# OTA.net
KiCad netlist of a schematic drawn in Altium Designer
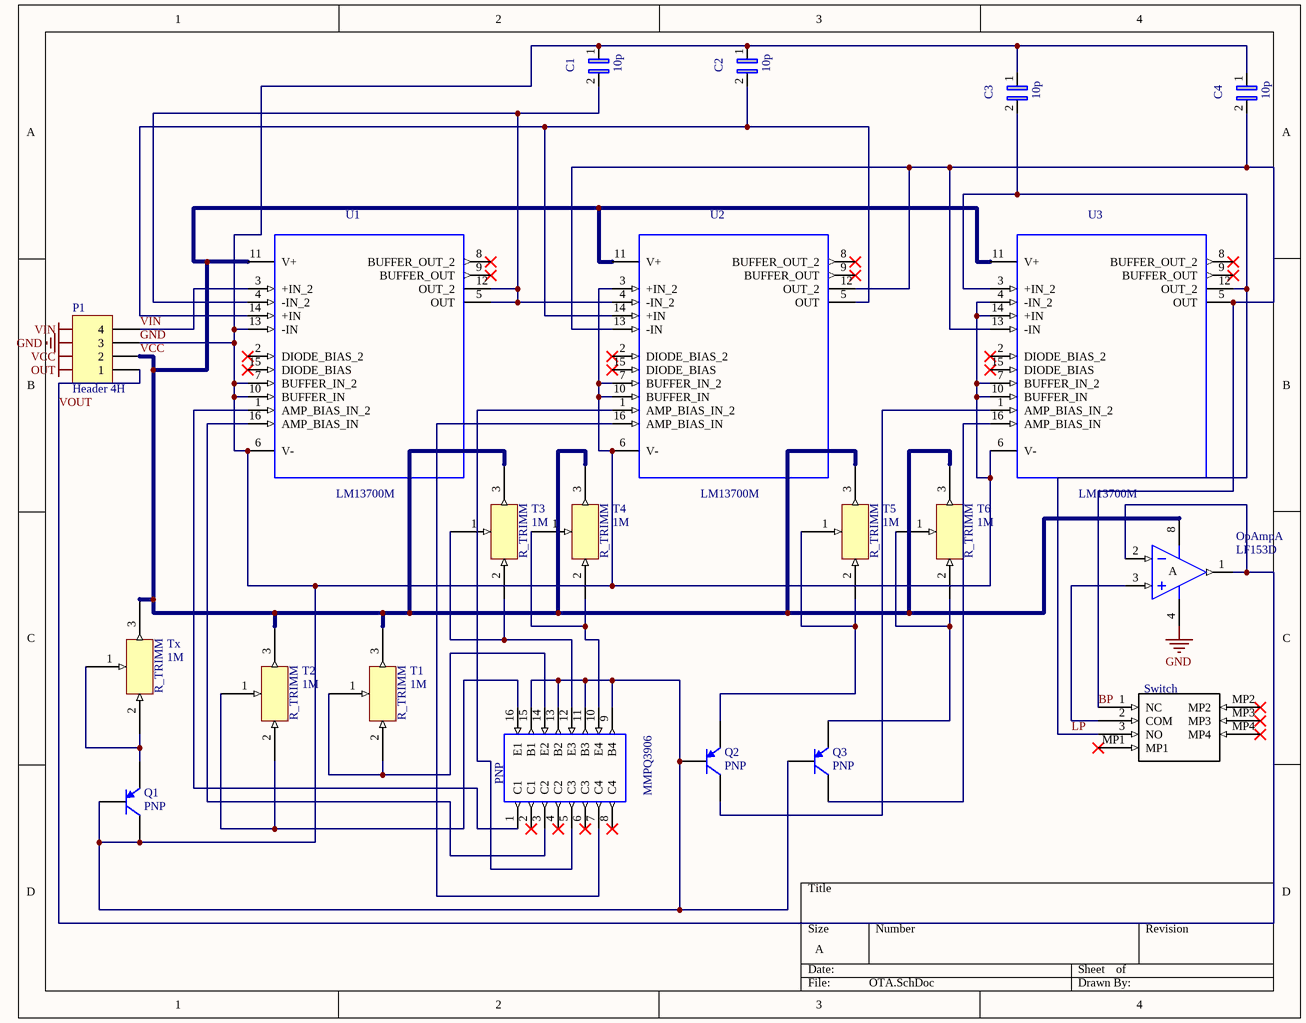
[diagram p0: OTA.SchDoc]

(export (version "E")
  (design (tool "Eeschema 10.0.6"))
  (components
    (comp (ref "C1")
      (value "10p")
      (footprint "_C*CAPC1005X55N_CC0402C100K5GACAUTO_CPrimary_C")
      (description "CAPACITOR CERAMIC 10 PF 10% TOL 50V C0G 0402")
      (fields (field (name "MF") "KEMET") (field (name "MP") "C0402C100K5GACAUTO"))
      (libsource (lib "*") (part "C0402C100K5GACAUTO"))
    )
    (comp (ref "C2")
      (value "10p")
      (footprint "_C*CAPC1005X55N_CC0402C100K5GACAUTO_CPrimary_C")
      (description "CAPACITOR CERAMIC 10 PF 10% TOL 50V C0G 0402")
      (fields (field (name "MF") "KEMET") (field (name "MP") "C0402C100K5GACAUTO"))
      (libsource (lib "*") (part "C0402C100K5GACAUTO"))
    )
    (comp (ref "C3")
      (value "10p")
      (footprint "_C*CAPC1005X55N_CC0402C100K5GACAUTO_CPrimary_C")
      (description "CAPACITOR CERAMIC 10 PF 10% TOL 50V C0G 0402")
      (fields (field (name "MF") "KEMET") (field (name "MP") "C0402C100K5GACAUTO"))
      (libsource (lib "*") (part "C0402C100K5GACAUTO"))
    )
    (comp (ref "C4")
      (value "10p")
      (footprint "_C*CAPC1005X55N_CC0402C100K5GACAUTO_CPrimary_C")
      (description "CAPACITOR CERAMIC 10 PF 10% TOL 50V C0G 0402")
      (fields (field (name "MF") "KEMET") (field (name "MP") "C0402C100K5GACAUTO"))
      (libsource (lib "*") (part "C0402C100K5GACAUTO"))
    )
    (comp (ref "OpAmp")
      (value "LF153D")
      (footprint "SO8_N")
      (description "Wide-Bandwidth Dual J-FET Operational Amplifier")
      (fields (field (name "PUBLISHER") "Altium Limited"))
      (libsource (lib "ST Operational Amplifier") (part "LF153D"))
    )
    (comp (ref "P1")
      (value "Header 4H")
      (footprint "HDR1X4H")
      (description "Header, 4-Pin, Right Angle")
      (fields (field (name "PUBLISHER") "Altium Limited"))
      (libsource (lib "Miscellaneous Connectors") (part "Header 4H"))
    )
    (comp (ref "PNP")
      (value "MMPQ3906")
      (footprint "LM13700LM13700MLM13700LM13700MLM13700PrimaryLM13700")
      (description "Dual Operational Transconductance Amplifier with Linearizing Diodes and Buffers 16-SOIC 0 to 70")
      (fields (field (name "MP") "LM13700M") (field (name "MF") "Texas Instruments"))
      (libsource (lib "MMPQ3906") (part "LM13700M"))
    )
    (comp (ref "Q1")
      (value "PNP")
      (footprint "SOT-23B")
      (description "PNP Bipolar Transistor")
      (fields (field (name "PUBLISHER") "Altium Limited"))
      (libsource (lib "Miscellaneous Devices") (part "PNP"))
    )
    (comp (ref "Q2")
      (value "PNP")
      (footprint "SOT-23B")
      (description "PNP Bipolar Transistor")
      (fields (field (name "PUBLISHER") "Altium Limited"))
      (libsource (lib "Miscellaneous Devices") (part "PNP"))
    )
    (comp (ref "Q3")
      (value "PNP")
      (footprint "SOT-23B")
      (description "PNP Bipolar Transistor")
      (fields (field (name "PUBLISHER") "Altium Limited"))
      (libsource (lib "Miscellaneous Devices") (part "PNP"))
    )
    (comp (ref "Switch")
      (value "~")
      (footprint "EG1215:PCBComponent_1")
      (libsource (lib "EG1215") (part "Component_1"))
    )
    (comp (ref "T1")
      (value "1M")
      (footprint "Trimmer:PCBComponent_1")
      (libsource (lib "*") (part "Component_1"))
    )
    (comp (ref "T2")
      (value "1M")
      (footprint "Trimmer:PCBComponent_1")
      (libsource (lib "*") (part "Component_1"))
    )
    (comp (ref "T3")
      (value "1M")
      (footprint "Trimmer:PCBComponent_1")
      (libsource (lib "*") (part "Component_1"))
    )
    (comp (ref "T4")
      (value "1M")
      (footprint "Trimmer:PCBComponent_1")
      (libsource (lib "*") (part "Component_1"))
    )
    (comp (ref "T5")
      (value "1M")
      (footprint "Trimmer:PCBComponent_1")
      (libsource (lib "*") (part "Component_1"))
    )
    (comp (ref "T6")
      (value "1M")
      (footprint "Trimmer:PCBComponent_1")
      (libsource (lib "*") (part "Component_1"))
    )
    (comp (ref "Tx")
      (value "1M")
      (footprint "Trimmer:PCBComponent_1")
      (libsource (lib "*") (part "Component_1"))
    )
    (comp (ref "U1")
      (value "LM13700M")
      (footprint "LM13700LM13700MLM13700LM13700MLM13700PrimaryLM13700")
      (description "Dual Operational Transconductance Amplifier with Linearizing Diodes and Buffers 16-SOIC 0 to 70")
      (fields (field (name "MF") "Texas Instruments"))
      (libsource (lib "*") (part "LM13700M"))
    )
    (comp (ref "U2")
      (value "LM13700M")
      (footprint "LM13700LM13700MLM13700LM13700MLM13700PrimaryLM13700")
      (description "Dual Operational Transconductance Amplifier with Linearizing Diodes and Buffers 16-SOIC 0 to 70")
      (fields (field (name "MF") "Texas Instruments"))
      (libsource (lib "*") (part "LM13700M"))
    )
    (comp (ref "U3")
      (value "LM13700M")
      (footprint "LM13700LM13700MLM13700LM13700MLM13700PrimaryLM13700")
      (description "Dual Operational Transconductance Amplifier with Linearizing Diodes and Buffers 16-SOIC 0 to 70")
      (fields (field (name "MF") "Texas Instruments"))
      (libsource (lib "*") (part "LM13700M"))
    )
  )
  (nets
    (net (code "1") (name "/BP") (class "Default")
      (node (ref "C4") (pin "2") (pinfunction "2_2") (pintype "passive"))
      (node (ref "Switch") (pin "1") (pinfunction "NC_1") (pintype "input"))
      (node (ref "U2") (pin "12") (pinfunction "OUT_2_12") (pintype "passive"))
      (node (ref "U2") (pin "13") (pinfunction "-IN_13") (pintype "input"))
      (node (ref "U3") (pin "13") (pinfunction "-IN_13") (pintype "input"))
      (node (ref "U3") (pin "5") (pinfunction "OUT_5") (pintype "passive"))
    )
    (net (code "2") (name "/LP") (class "Default")
      (node (ref "C3") (pin "2") (pinfunction "2_2") (pintype "passive"))
      (node (ref "Switch") (pin "3") (pinfunction "NO_3") (pintype "input"))
      (node (ref "U3") (pin "12") (pinfunction "OUT_2_12") (pintype "passive"))
      (node (ref "U3") (pin "3") (pinfunction "+IN_2_3") (pintype "input"))
    )
    (net (code "3") (name "/VOUT") (class "Default")
      (node (ref "OpAmp") (pin "1") (pinfunction "OUT_1") (pintype "output"))
      (node (ref "OpAmp") (pin "2") (pinfunction "IN-_2") (pintype "input"))
      (node (ref "P1") (pin "1") (pinfunction "1_1") (pintype "passive"))
    )
    (net (code "4") (name "GND") (class "Default")
      (node (ref "C1") (pin "1") (pinfunction "1_1") (pintype "passive"))
      (node (ref "C2") (pin "1") (pinfunction "1_1") (pintype "passive"))
      (node (ref "C3") (pin "1") (pinfunction "1_1") (pintype "passive"))
      (node (ref "C4") (pin "1") (pinfunction "1_1") (pintype "passive"))
      (node (ref "OpAmp") (pin "4") (pinfunction "V-_4") (pintype "power_in"))
      (node (ref "P1") (pin "3") (pinfunction "3_3") (pintype "passive"))
      (node (ref "PNP") (pin "11") (pinfunction "B3_11") (pintype "output"))
      (node (ref "PNP") (pin "13") (pinfunction "B2_13") (pintype "output"))
      (node (ref "PNP") (pin "15") (pinfunction "B1_15") (pintype "output"))
      (node (ref "PNP") (pin "9") (pinfunction "B4_9") (pintype "output"))
      (node (ref "Q1") (pin "1") (pinfunction "C_1") (pintype "passive"))
      (node (ref "Q1") (pin "2") (pinfunction "B_2") (pintype "passive"))
      (node (ref "Q2") (pin "2") (pinfunction "B_2") (pintype "passive"))
      (node (ref "Q3") (pin "2") (pinfunction "B_2") (pintype "passive"))
      (node (ref "U1") (pin "10") (pinfunction "BUFFER_IN_10") (pintype "input"))
      (node (ref "U1") (pin "13") (pinfunction "-IN_13") (pintype "input"))
      (node (ref "U1") (pin "6") (pinfunction "V-_6") (pintype "power_in"))
      (node (ref "U1") (pin "7") (pinfunction "BUFFER_IN_2_7") (pintype "input"))
      (node (ref "U2") (pin "10") (pinfunction "BUFFER_IN_10") (pintype "input"))
      (node (ref "U2") (pin "3") (pinfunction "+IN_2_3") (pintype "input"))
      (node (ref "U2") (pin "6") (pinfunction "V-_6") (pintype "power_in"))
      (node (ref "U2") (pin "7") (pinfunction "BUFFER_IN_2_7") (pintype "input"))
      (node (ref "U3") (pin "10") (pinfunction "BUFFER_IN_10") (pintype "input"))
      (node (ref "U3") (pin "14") (pinfunction "+IN_14") (pintype "input"))
      (node (ref "U3") (pin "4") (pinfunction "-IN_2_4") (pintype "input"))
      (node (ref "U3") (pin "6") (pinfunction "V-_6") (pintype "power_in"))
      (node (ref "U3") (pin "7") (pinfunction "BUFFER_IN_2_7") (pintype "input"))
    )
    (net (code "5") (name "Net-(OpAmpA-IN+)") (class "Default")
      (node (ref "OpAmp") (pin "3") (pinfunction "IN+_3") (pintype "input"))
      (node (ref "Switch") (pin "2") (pinfunction "COM_2") (pintype "input"))
    )
    (net (code "6") (name "Net-(PNP-E1)") (class "Default")
      (node (ref "PNP") (pin "16") (pinfunction "E1_16") (pintype "input"))
      (node (ref "T2") (pin "1") (pintype "input"))
      (node (ref "T2") (pin "2") (pintype "input"))
    )
    (net (code "7") (name "Net-(PNP-E2)") (class "Default")
      (node (ref "PNP") (pin "14") (pinfunction "E2_14") (pintype "input"))
      (node (ref "T1") (pin "1") (pintype "input"))
      (node (ref "T1") (pin "2") (pintype "input"))
    )
    (net (code "8") (name "Net-(PNP-E3)") (class "Default")
      (node (ref "PNP") (pin "12") (pinfunction "E3_12") (pintype "input"))
      (node (ref "T3") (pin "1") (pintype "input"))
      (node (ref "T3") (pin "2") (pintype "input"))
    )
    (net (code "9") (name "Net-(PNP-E4)") (class "Default")
      (node (ref "PNP") (pin "10") (pinfunction "E4_10") (pintype "input"))
      (node (ref "T4") (pin "1") (pintype "input"))
      (node (ref "T4") (pin "2") (pintype "input"))
    )
    (net (code "10") (name "Net-(Q1-E)") (class "Default")
      (node (ref "Q1") (pin "3") (pinfunction "E_3") (pintype "passive"))
      (node (ref "Tx") (pin "1") (pintype "input"))
      (node (ref "Tx") (pin "2") (pintype "input"))
    )
    (net (code "11") (name "Net-(Q2-C)") (class "Default")
      (node (ref "Q2") (pin "1") (pinfunction "C_1") (pintype "passive"))
      (node (ref "U3") (pin "1") (pinfunction "AMP_BIAS_IN_2_1") (pintype "input"))
    )
    (net (code "12") (name "Net-(Q2-E)") (class "Default")
      (node (ref "Q2") (pin "3") (pinfunction "E_3") (pintype "passive"))
      (node (ref "T5") (pin "1") (pintype "input"))
      (node (ref "T5") (pin "2") (pintype "input"))
    )
    (net (code "13") (name "Net-(Q3-C)") (class "Default")
      (node (ref "Q3") (pin "1") (pinfunction "C_1") (pintype "passive"))
      (node (ref "U3") (pin "16") (pinfunction "AMP_BIAS_IN_16") (pintype "input"))
    )
    (net (code "14") (name "Net-(Q3-E)") (class "Default")
      (node (ref "Q3") (pin "3") (pinfunction "E_3") (pintype "passive"))
      (node (ref "T6") (pin "1") (pintype "input"))
      (node (ref "T6") (pin "2") (pintype "input"))
    )
    (net (code "15") (name "Net-(U1-+IN)") (class "Default")
      (node (ref "C2") (pin "2") (pinfunction "2_2") (pintype "passive"))
      (node (ref "U1") (pin "14") (pinfunction "+IN_14") (pintype "input"))
      (node (ref "U2") (pin "14") (pinfunction "+IN_14") (pintype "input"))
      (node (ref "U2") (pin "5") (pinfunction "OUT_5") (pintype "passive"))
    )
    (net (code "16") (name "Net-(U1--IN_2)") (class "Default")
      (node (ref "C1") (pin "2") (pinfunction "2_2") (pintype "passive"))
      (node (ref "U1") (pin "12") (pinfunction "OUT_2_12") (pintype "passive"))
      (node (ref "U1") (pin "4") (pinfunction "-IN_2_4") (pintype "input"))
      (node (ref "U1") (pin "5") (pinfunction "OUT_5") (pintype "passive"))
      (node (ref "U2") (pin "4") (pinfunction "-IN_2_4") (pintype "input"))
    )
    (net (code "17") (name "Net-(U1-AMP_BIAS_IN)") (class "Default")
      (node (ref "PNP") (pin "3") (pinfunction "C2_3") (pintype "output"))
      (node (ref "U1") (pin "16") (pinfunction "AMP_BIAS_IN_16") (pintype "input"))
    )
    (net (code "18") (name "Net-(U1-AMP_BIAS_IN_2)") (class "Default")
      (node (ref "PNP") (pin "1") (pinfunction "C1_1") (pintype "output"))
      (node (ref "U1") (pin "1") (pinfunction "AMP_BIAS_IN_2_1") (pintype "input"))
    )
    (net (code "19") (name "Net-(U2-AMP_BIAS_IN)") (class "Default")
      (node (ref "PNP") (pin "7") (pinfunction "C4_7") (pintype "output"))
      (node (ref "U2") (pin "16") (pinfunction "AMP_BIAS_IN_16") (pintype "input"))
    )
    (net (code "20") (name "Net-(U2-AMP_BIAS_IN_2)") (class "Default")
      (node (ref "PNP") (pin "5") (pinfunction "C3_5") (pintype "output"))
      (node (ref "U2") (pin "1") (pinfunction "AMP_BIAS_IN_2_1") (pintype "input"))
    )
    (net (code "22") (name "VCC") (class "Default")
      (node (ref "OpAmp") (pin "8") (pinfunction "V+_8") (pintype "power_in"))
      (node (ref "P1") (pin "2") (pinfunction "2_2") (pintype "passive"))
      (node (ref "T1") (pin "3") (pintype "output"))
      (node (ref "T2") (pin "3") (pintype "output"))
      (node (ref "T3") (pin "3") (pintype "output"))
      (node (ref "T4") (pin "3") (pintype "output"))
      (node (ref "T5") (pin "3") (pintype "output"))
      (node (ref "T6") (pin "3") (pintype "output"))
      (node (ref "Tx") (pin "3") (pintype "output"))
      (node (ref "U1") (pin "11") (pinfunction "V+_11") (pintype "power_in"))
      (node (ref "U2") (pin "11") (pinfunction "V+_11") (pintype "power_in"))
      (node (ref "U3") (pin "11") (pinfunction "V+_11") (pintype "power_in"))
    )
    (net (code "23") (name "VIN") (class "Default")
      (node (ref "P1") (pin "4") (pinfunction "4_4") (pintype "passive"))
      (node (ref "U1") (pin "3") (pinfunction "+IN_2_3") (pintype "input"))
    )
    (net (code "24") (name "unconnected-(PNP-C1-Pad2)") (class "Default")
      (node (ref "PNP") (pin "2") (pinfunction "C1_2") (pintype "output+no_connect"))
    )
    (net (code "25") (name "unconnected-(PNP-C2-Pad4)") (class "Default")
      (node (ref "PNP") (pin "4") (pinfunction "C2_4") (pintype "output+no_connect"))
    )
    (net (code "26") (name "unconnected-(PNP-C3-Pad6)") (class "Default")
      (node (ref "PNP") (pin "6") (pinfunction "C3_6") (pintype "output+no_connect"))
    )
    (net (code "27") (name "unconnected-(PNP-C4-Pad8)") (class "Default")
      (node (ref "PNP") (pin "8") (pinfunction "C4_8") (pintype "output+no_connect"))
    )
    (net (code "28") (name "unconnected-(Switch-PadMP1)") (class "Default")
      (node (ref "Switch") (pin "MP1") (pinfunction "MP1_MP1") (pintype "input+no_connect"))
    )
    (net (code "29") (name "unconnected-(Switch-PadMP2)") (class "Default")
      (node (ref "Switch") (pin "MP2") (pinfunction "MP2_MP2") (pintype "input+no_connect"))
    )
    (net (code "30") (name "unconnected-(Switch-PadMP3)") (class "Default")
      (node (ref "Switch") (pin "MP3") (pinfunction "MP3_MP3") (pintype "input+no_connect"))
    )
    (net (code "31") (name "unconnected-(Switch-PadMP4)") (class "Default")
      (node (ref "Switch") (pin "MP4") (pinfunction "MP4_MP4") (pintype "input+no_connect"))
    )
    (net (code "32") (name "unconnected-(U1-BUFFER_OUT-Pad9)") (class "Default")
      (node (ref "U1") (pin "9") (pinfunction "BUFFER_OUT_9") (pintype "output+no_connect"))
    )
    (net (code "33") (name "unconnected-(U1-BUFFER_OUT_2-Pad8)") (class "Default")
      (node (ref "U1") (pin "8") (pinfunction "BUFFER_OUT_2_8") (pintype "output+no_connect"))
    )
    (net (code "34") (name "unconnected-(U1-DIODE_BIAS-Pad15)") (class "Default")
      (node (ref "U1") (pin "15") (pinfunction "DIODE_BIAS_15") (pintype "input+no_connect"))
    )
    (net (code "35") (name "unconnected-(U1-DIODE_BIAS_2-Pad2)") (class "Default")
      (node (ref "U1") (pin "2") (pinfunction "DIODE_BIAS_2_2") (pintype "input+no_connect"))
    )
    (net (code "36") (name "unconnected-(U2-BUFFER_OUT-Pad9)") (class "Default")
      (node (ref "U2") (pin "9") (pinfunction "BUFFER_OUT_9") (pintype "output+no_connect"))
    )
    (net (code "37") (name "unconnected-(U2-BUFFER_OUT_2-Pad8)") (class "Default")
      (node (ref "U2") (pin "8") (pinfunction "BUFFER_OUT_2_8") (pintype "output+no_connect"))
    )
    (net (code "38") (name "unconnected-(U2-DIODE_BIAS-Pad15)") (class "Default")
      (node (ref "U2") (pin "15") (pinfunction "DIODE_BIAS_15") (pintype "input+no_connect"))
    )
    (net (code "39") (name "unconnected-(U2-DIODE_BIAS_2-Pad2)") (class "Default")
      (node (ref "U2") (pin "2") (pinfunction "DIODE_BIAS_2_2") (pintype "input+no_connect"))
    )
    (net (code "40") (name "unconnected-(U3-BUFFER_OUT-Pad9)") (class "Default")
      (node (ref "U3") (pin "9") (pinfunction "BUFFER_OUT_9") (pintype "output+no_connect"))
    )
    (net (code "41") (name "unconnected-(U3-BUFFER_OUT_2-Pad8)") (class "Default")
      (node (ref "U3") (pin "8") (pinfunction "BUFFER_OUT_2_8") (pintype "output+no_connect"))
    )
    (net (code "42") (name "unconnected-(U3-DIODE_BIAS-Pad15)") (class "Default")
      (node (ref "U3") (pin "15") (pinfunction "DIODE_BIAS_15") (pintype "input+no_connect"))
    )
    (net (code "43") (name "unconnected-(U3-DIODE_BIAS_2-Pad2)") (class "Default")
      (node (ref "U3") (pin "2") (pinfunction "DIODE_BIAS_2_2") (pintype "input+no_connect"))
    )
  )
)
